# teatimer.net
KiCad netlist of a schematic drawn in EAGLE
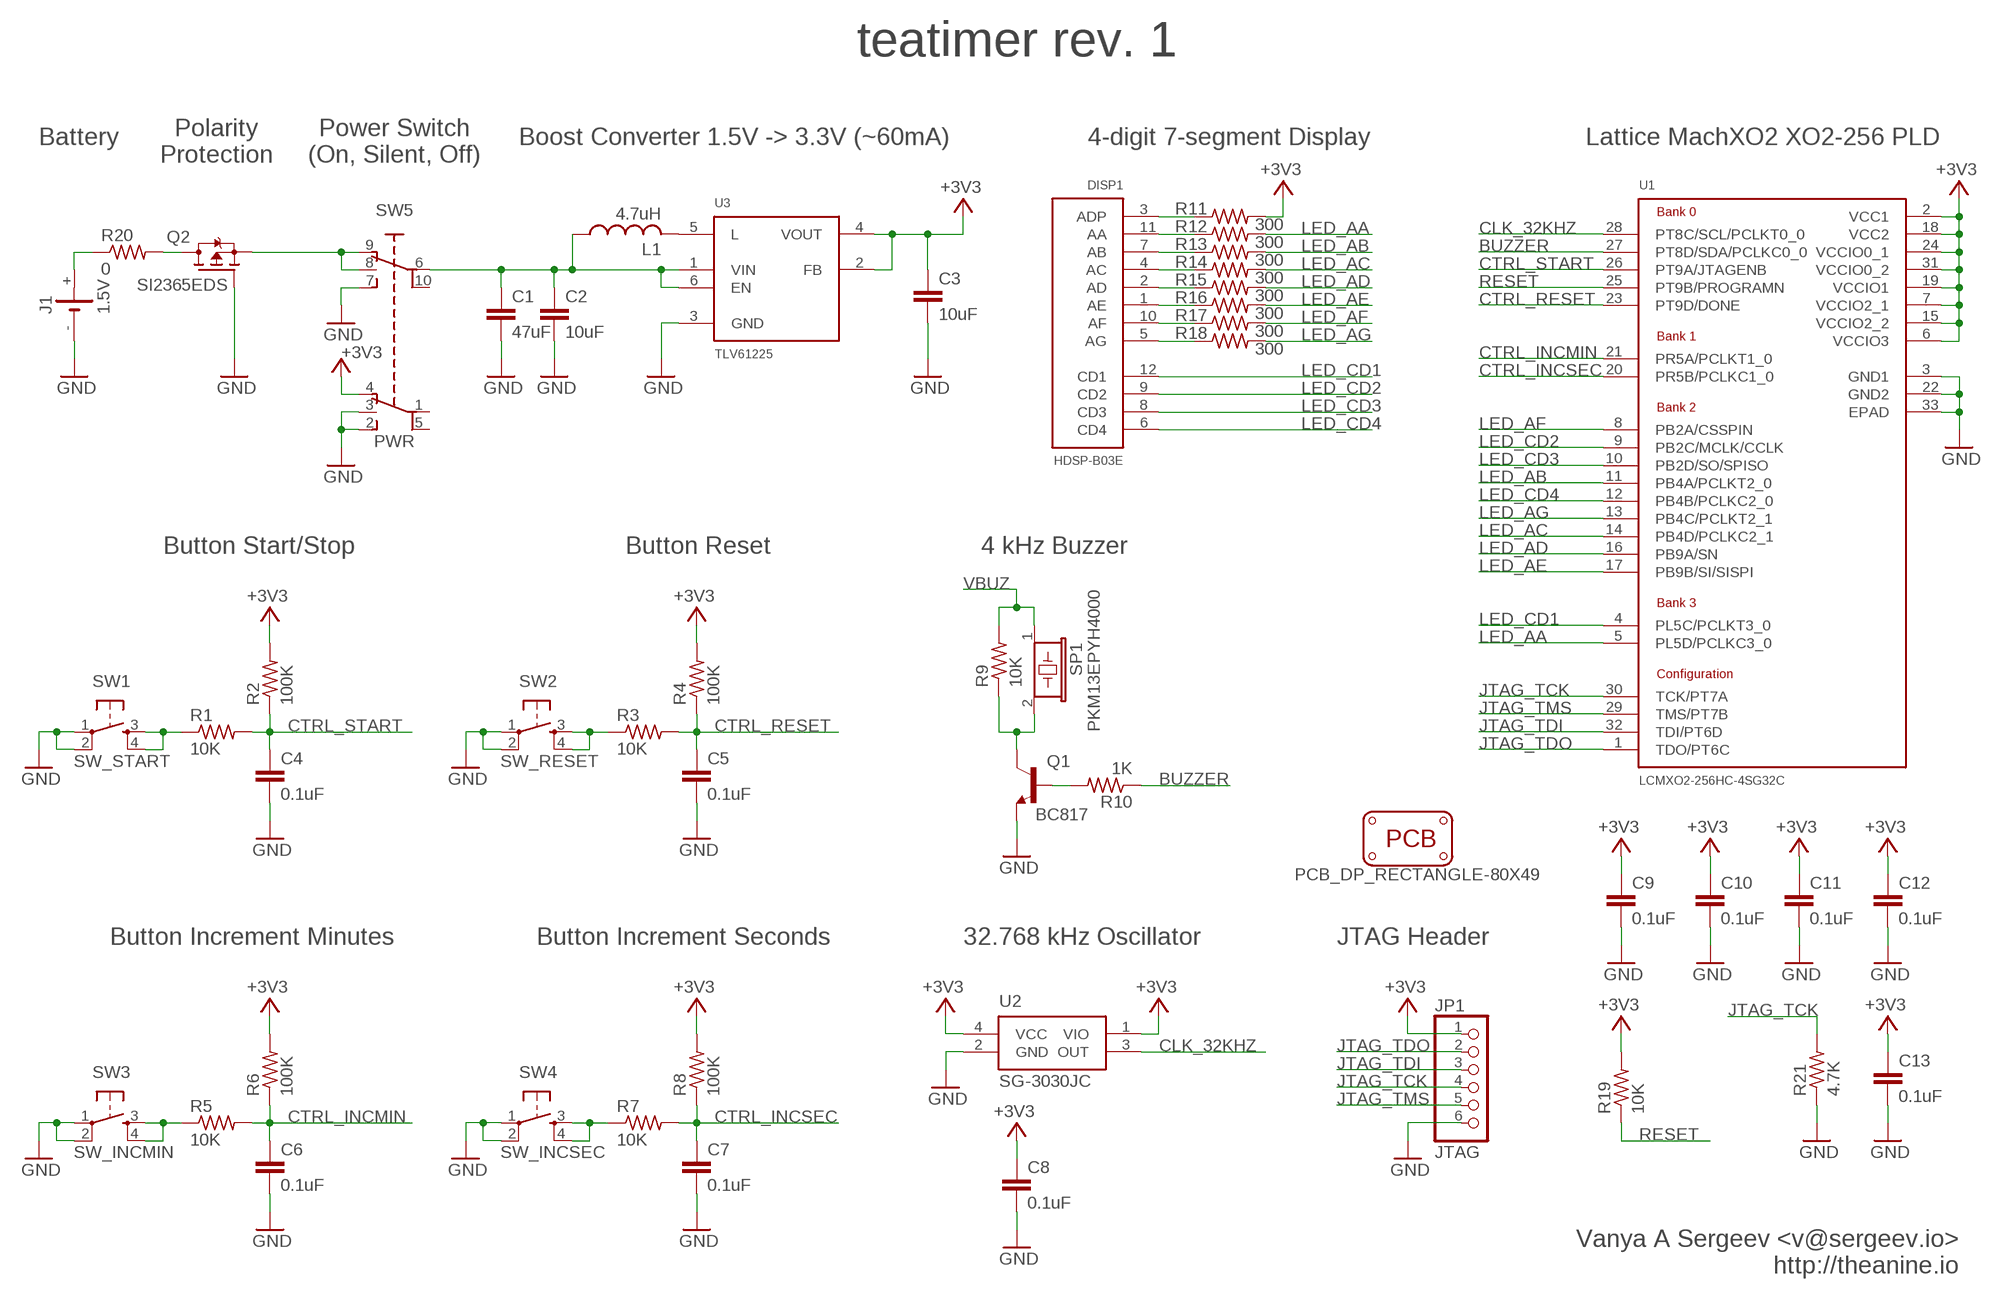
[diagram p0: schematic, sheet 1]

(export (version "E")
  (design (tool "Eeschema 10.0.6"))
  (components
    (comp (ref "C1")
      (value "47uF")
      (footprint "eagle-import:C0805")
      (libsource (lib "eagle-import") (part "C-EUC0805"))
    )
    (comp (ref "C2")
      (value "10uF")
      (footprint "eagle-import:C0603")
      (libsource (lib "eagle-import") (part "C-EUC0603"))
    )
    (comp (ref "C3")
      (value "10uF")
      (footprint "eagle-import:C0603")
      (libsource (lib "eagle-import") (part "C-EUC0603"))
    )
    (comp (ref "C4")
      (value "0.1uF")
      (footprint "eagle-import:C0603")
      (libsource (lib "eagle-import") (part "C-EUC0603"))
    )
    (comp (ref "C5")
      (value "0.1uF")
      (footprint "eagle-import:C0603")
      (libsource (lib "eagle-import") (part "C-EUC0603"))
    )
    (comp (ref "C6")
      (value "0.1uF")
      (footprint "eagle-import:C0603")
      (libsource (lib "eagle-import") (part "C-EUC0603"))
    )
    (comp (ref "C7")
      (value "0.1uF")
      (footprint "eagle-import:C0603")
      (libsource (lib "eagle-import") (part "C-EUC0603"))
    )
    (comp (ref "C8")
      (value "0.1uF")
      (footprint "eagle-import:C0603")
      (libsource (lib "eagle-import") (part "C-EUC0603"))
    )
    (comp (ref "C9")
      (value "0.1uF")
      (footprint "eagle-import:C0603")
      (libsource (lib "eagle-import") (part "C-EUC0603"))
    )
    (comp (ref "C10")
      (value "0.1uF")
      (footprint "eagle-import:C0603")
      (libsource (lib "eagle-import") (part "C-EUC0603"))
    )
    (comp (ref "C11")
      (value "0.1uF")
      (footprint "eagle-import:C0603")
      (libsource (lib "eagle-import") (part "C-EUC0603"))
    )
    (comp (ref "C12")
      (value "0.1uF")
      (footprint "eagle-import:C0603")
      (libsource (lib "eagle-import") (part "C-EUC0603"))
    )
    (comp (ref "C13")
      (value "0.1uF")
      (footprint "eagle-import:C0603")
      (libsource (lib "eagle-import") (part "C-EUC0603"))
    )
    (comp (ref "DISP1")
      (value "HDSP-B03E")
      (footprint "eagle-import:HDSP-B0XE")
      (libsource (lib "eagle-import") (part "HDSP-B03E"))
    )
    (comp (ref "J1")
      (value "1.5V")
      (footprint "eagle-import:AAA-2466")
      (libsource (lib "eagle-import") (part "BAT-HOLDER-AAA"))
    )
    (comp (ref "JP1")
      (value "JTAG")
      (footprint "eagle-import:1X06_90-SMD")
      (libsource (lib "eagle-import") (part "PINHD-1X6"))
    )
    (comp (ref "L1")
      (value "4.7uH")
      (footprint "eagle-import:L2520")
      (libsource (lib "eagle-import") (part "CIG22L"))
    )
    (comp (ref "PCB1")
      (value "PCB_DP_RECTANGLE-80X49")
      (footprint "eagle-import:DP8049_V1")
      (libsource (lib "eagle-import") (part "PCB_DP_RECTANGLE-80X49"))
    )
    (comp (ref "Q1")
      (value "BC817")
      (footprint "eagle-import:SOT23-BEC")
      (libsource (lib "eagle-import") (part "BC817SMD-40"))
    )
    (comp (ref "Q2")
      (value "SI2365EDS")
      (footprint "eagle-import:SOT23")
      (libsource (lib "eagle-import") (part "SI2365EDS"))
    )
    (comp (ref "R1")
      (value "10K")
      (footprint "eagle-import:R0603")
      (libsource (lib "eagle-import") (part "R-US_R0603"))
    )
    (comp (ref "R2")
      (value "100K")
      (footprint "eagle-import:R0603")
      (libsource (lib "eagle-import") (part "R-US_R0603"))
    )
    (comp (ref "R3")
      (value "10K")
      (footprint "eagle-import:R0603")
      (libsource (lib "eagle-import") (part "R-US_R0603"))
    )
    (comp (ref "R4")
      (value "100K")
      (footprint "eagle-import:R0603")
      (libsource (lib "eagle-import") (part "R-US_R0603"))
    )
    (comp (ref "R5")
      (value "10K")
      (footprint "eagle-import:R0603")
      (libsource (lib "eagle-import") (part "R-US_R0603"))
    )
    (comp (ref "R6")
      (value "100K")
      (footprint "eagle-import:R0603")
      (libsource (lib "eagle-import") (part "R-US_R0603"))
    )
    (comp (ref "R7")
      (value "10K")
      (footprint "eagle-import:R0603")
      (libsource (lib "eagle-import") (part "R-US_R0603"))
    )
    (comp (ref "R8")
      (value "100K")
      (footprint "eagle-import:R0603")
      (libsource (lib "eagle-import") (part "R-US_R0603"))
    )
    (comp (ref "R9")
      (value "10K")
      (footprint "eagle-import:R0603")
      (libsource (lib "eagle-import") (part "R-US_R0603"))
    )
    (comp (ref "R10")
      (value "1K")
      (footprint "eagle-import:R0603")
      (libsource (lib "eagle-import") (part "R-US_R0603"))
    )
    (comp (ref "R11")
      (value "300")
      (footprint "eagle-import:R0603")
      (libsource (lib "eagle-import") (part "R-US_R0603"))
    )
    (comp (ref "R12")
      (value "300")
      (footprint "eagle-import:R0603")
      (libsource (lib "eagle-import") (part "R-US_R0603"))
    )
    (comp (ref "R13")
      (value "300")
      (footprint "eagle-import:R0603")
      (libsource (lib "eagle-import") (part "R-US_R0603"))
    )
    (comp (ref "R14")
      (value "300")
      (footprint "eagle-import:R0603")
      (libsource (lib "eagle-import") (part "R-US_R0603"))
    )
    (comp (ref "R15")
      (value "300")
      (footprint "eagle-import:R0603")
      (libsource (lib "eagle-import") (part "R-US_R0603"))
    )
    (comp (ref "R16")
      (value "300")
      (footprint "eagle-import:R0603")
      (libsource (lib "eagle-import") (part "R-US_R0603"))
    )
    (comp (ref "R17")
      (value "300")
      (footprint "eagle-import:R0603")
      (libsource (lib "eagle-import") (part "R-US_R0603"))
    )
    (comp (ref "R18")
      (value "300")
      (footprint "eagle-import:R0603")
      (libsource (lib "eagle-import") (part "R-US_R0603"))
    )
    (comp (ref "R19")
      (value "10K")
      (footprint "eagle-import:R0603")
      (libsource (lib "eagle-import") (part "R-US_R0603"))
    )
    (comp (ref "R20")
      (value "0")
      (footprint "eagle-import:R0603")
      (libsource (lib "eagle-import") (part "R-US_R0603"))
    )
    (comp (ref "R21")
      (value "4.7K")
      (footprint "eagle-import:R0603")
      (libsource (lib "eagle-import") (part "R-US_R0603"))
    )
    (comp (ref "SP1")
      (value "PKM13EPYH4000")
      (footprint "eagle-import:PKM13EPYH4000")
      (libsource (lib "eagle-import") (part "PKM13EPYH4000"))
    )
    (comp (ref "SW1")
      (value "SW_START")
      (footprint "eagle-import:PTS645")
      (libsource (lib "eagle-import") (part "PTS645"))
    )
    (comp (ref "SW2")
      (value "SW_RESET")
      (footprint "eagle-import:PTS645")
      (libsource (lib "eagle-import") (part "PTS645"))
    )
    (comp (ref "SW3")
      (value "SW_INCMIN")
      (footprint "eagle-import:PTS645")
      (libsource (lib "eagle-import") (part "PTS645"))
    )
    (comp (ref "SW4")
      (value "SW_INCSEC")
      (footprint "eagle-import:PTS645")
      (libsource (lib "eagle-import") (part "PTS645"))
    )
    (comp (ref "SW5")
      (value "PWR")
      (footprint "eagle-import:OS203011MV9QN1")
      (libsource (lib "eagle-import") (part "OS203011MV9QN1"))
    )
    (comp (ref "U1")
      (value "LCMXO2-256HC-4SG32C")
      (footprint "eagle-import:QFN32G-0.5-5X5MM")
      (libsource (lib "eagle-import") (part "LCMXO2-256HC-4SG32C"))
    )
    (comp (ref "U2")
      (value "SG-3030JC")
      (footprint "eagle-import:SG-3030JC")
      (libsource (lib "eagle-import") (part "SG-3030JC"))
    )
    (comp (ref "U3")
      (value "TLV61225")
      (footprint "eagle-import:SC70-6L")
      (libsource (lib "eagle-import") (part "TLV61225"))
    )
  )
  (nets
    (net (code "1") (name "+3V3") (class "Default")
      (node (ref "C10") (pin "1") (pinfunction "1_1") (pintype "passive"))
      (node (ref "C11") (pin "1") (pinfunction "1_1") (pintype "passive"))
      (node (ref "C12") (pin "1") (pinfunction "1_1") (pintype "passive"))
      (node (ref "C13") (pin "1") (pinfunction "1_1") (pintype "passive"))
      (node (ref "C3") (pin "1") (pinfunction "1_1") (pintype "passive"))
      (node (ref "C8") (pin "1") (pinfunction "1_1") (pintype "passive"))
      (node (ref "C9") (pin "1") (pinfunction "1_1") (pintype "passive"))
      (node (ref "JP1") (pin "1") (pinfunction "1_1") (pintype "passive"))
      (node (ref "R11") (pin "2") (pinfunction "2_2") (pintype "passive"))
      (node (ref "R19") (pin "2") (pinfunction "2_2") (pintype "passive"))
      (node (ref "R2") (pin "2") (pinfunction "2_2") (pintype "passive"))
      (node (ref "R4") (pin "2") (pinfunction "2_2") (pintype "passive"))
      (node (ref "R6") (pin "2") (pinfunction "2_2") (pintype "passive"))
      (node (ref "R8") (pin "2") (pinfunction "2_2") (pintype "passive"))
      (node (ref "SW5") (pin "4") (pinfunction "B1_4") (pintype "passive"))
      (node (ref "U1") (pin "15") (pinfunction "VCCIO2_2_15") (pintype "bidirectional"))
      (node (ref "U1") (pin "18") (pinfunction "VCC2_18") (pintype "bidirectional"))
      (node (ref "U1") (pin "19") (pinfunction "VCCIO1_19") (pintype "bidirectional"))
      (node (ref "U1") (pin "2") (pinfunction "VCC1_2") (pintype "bidirectional"))
      (node (ref "U1") (pin "24") (pinfunction "VCCIO0_1_24") (pintype "bidirectional"))
      (node (ref "U1") (pin "31") (pinfunction "VCCIO0_2_31") (pintype "bidirectional"))
      (node (ref "U1") (pin "6") (pinfunction "VCCIO3_6") (pintype "bidirectional"))
      (node (ref "U1") (pin "7") (pinfunction "VCCIO2_1_7") (pintype "bidirectional"))
      (node (ref "U2") (pin "1") (pinfunction "VIO_1") (pintype "bidirectional"))
      (node (ref "U2") (pin "4") (pinfunction "VCC_4") (pintype "bidirectional"))
      (node (ref "U3") (pin "2") (pinfunction "FB_2") (pintype "bidirectional"))
      (node (ref "U3") (pin "4") (pinfunction "VOUT_4") (pintype "bidirectional"))
    )
    (net (code "2") (name "/BUZZER") (class "Default")
      (node (ref "R10") (pin "1") (pinfunction "1_1") (pintype "passive"))
      (node (ref "U1") (pin "27") (pinfunction "PT8D/SDA/PCLKC0_0_27") (pintype "bidirectional"))
    )
    (net (code "3") (name "/CLK_32KHZ") (class "Default")
      (node (ref "U1") (pin "28") (pinfunction "PT8C/SCL/PCLKT0_0_28") (pintype "bidirectional"))
      (node (ref "U2") (pin "3") (pinfunction "OUT_3") (pintype "bidirectional"))
    )
    (net (code "4") (name "/CTRL_INCMIN") (class "Default")
      (node (ref "C6") (pin "1") (pinfunction "1_1") (pintype "passive"))
      (node (ref "R5") (pin "2") (pinfunction "2_2") (pintype "passive"))
      (node (ref "R6") (pin "1") (pinfunction "1_1") (pintype "passive"))
      (node (ref "U1") (pin "21") (pinfunction "PR5A/PCLKT1_0_21") (pintype "bidirectional"))
    )
    (net (code "5") (name "/CTRL_INCSEC") (class "Default")
      (node (ref "C7") (pin "1") (pinfunction "1_1") (pintype "passive"))
      (node (ref "R7") (pin "2") (pinfunction "2_2") (pintype "passive"))
      (node (ref "R8") (pin "1") (pinfunction "1_1") (pintype "passive"))
      (node (ref "U1") (pin "20") (pinfunction "PR5B/PCLKC1_0_20") (pintype "bidirectional"))
    )
    (net (code "6") (name "/CTRL_RESET") (class "Default")
      (node (ref "C5") (pin "1") (pinfunction "1_1") (pintype "passive"))
      (node (ref "R3") (pin "2") (pinfunction "2_2") (pintype "passive"))
      (node (ref "R4") (pin "1") (pinfunction "1_1") (pintype "passive"))
      (node (ref "U1") (pin "23") (pinfunction "PT9D/DONE_23") (pintype "bidirectional"))
    )
    (net (code "7") (name "/CTRL_START") (class "Default")
      (node (ref "C4") (pin "1") (pinfunction "1_1") (pintype "passive"))
      (node (ref "R1") (pin "2") (pinfunction "2_2") (pintype "passive"))
      (node (ref "R2") (pin "1") (pinfunction "1_1") (pintype "passive"))
      (node (ref "U1") (pin "26") (pinfunction "PT9A/JTAGENB_26") (pintype "bidirectional"))
    )
    (net (code "8") (name "/JTAG_TCK") (class "Default")
      (node (ref "JP1") (pin "4") (pinfunction "4_4") (pintype "passive"))
      (node (ref "R21") (pin "2") (pinfunction "2_2") (pintype "passive"))
      (node (ref "U1") (pin "30") (pinfunction "TCK/PT7A_30") (pintype "bidirectional"))
    )
    (net (code "9") (name "/JTAG_TDI") (class "Default")
      (node (ref "JP1") (pin "3") (pinfunction "3_3") (pintype "passive"))
      (node (ref "U1") (pin "32") (pinfunction "TDI/PT6D_32") (pintype "bidirectional"))
    )
    (net (code "10") (name "/JTAG_TDO") (class "Default")
      (node (ref "JP1") (pin "2") (pinfunction "2_2") (pintype "passive"))
      (node (ref "U1") (pin "1") (pinfunction "TDO/PT6C_1") (pintype "bidirectional"))
    )
    (net (code "11") (name "/JTAG_TMS") (class "Default")
      (node (ref "JP1") (pin "5") (pinfunction "5_5") (pintype "passive"))
      (node (ref "U1") (pin "29") (pinfunction "TMS/PT7B_29") (pintype "bidirectional"))
    )
    (net (code "12") (name "/LED_AA") (class "Default")
      (node (ref "R12") (pin "2") (pinfunction "2_2") (pintype "passive"))
      (node (ref "U1") (pin "5") (pinfunction "PL5D/PCLKC3_0_5") (pintype "bidirectional"))
    )
    (net (code "13") (name "/LED_AB") (class "Default")
      (node (ref "R13") (pin "2") (pinfunction "2_2") (pintype "passive"))
      (node (ref "U1") (pin "11") (pinfunction "PB4A/PCLKT2_0_11") (pintype "bidirectional"))
    )
    (net (code "14") (name "/LED_AC") (class "Default")
      (node (ref "R14") (pin "2") (pinfunction "2_2") (pintype "passive"))
      (node (ref "U1") (pin "14") (pinfunction "PB4D/PCLKC2_1_14") (pintype "bidirectional"))
    )
    (net (code "15") (name "/LED_AD") (class "Default")
      (node (ref "R15") (pin "2") (pinfunction "2_2") (pintype "passive"))
      (node (ref "U1") (pin "16") (pinfunction "PB9A/SN_16") (pintype "bidirectional"))
    )
    (net (code "16") (name "/LED_AE") (class "Default")
      (node (ref "R16") (pin "2") (pinfunction "2_2") (pintype "passive"))
      (node (ref "U1") (pin "17") (pinfunction "PB9B/SI/SISPI_17") (pintype "bidirectional"))
    )
    (net (code "17") (name "/LED_AF") (class "Default")
      (node (ref "R17") (pin "2") (pinfunction "2_2") (pintype "passive"))
      (node (ref "U1") (pin "8") (pinfunction "PB2A/CSSPIN_8") (pintype "bidirectional"))
    )
    (net (code "18") (name "/LED_AG") (class "Default")
      (node (ref "R18") (pin "2") (pinfunction "2_2") (pintype "passive"))
      (node (ref "U1") (pin "13") (pinfunction "PB4C/PCLKT2_1_13") (pintype "bidirectional"))
    )
    (net (code "19") (name "/LED_CD1") (class "Default")
      (node (ref "DISP1") (pin "12") (pinfunction "CD1_12") (pintype "bidirectional"))
      (node (ref "U1") (pin "4") (pinfunction "PL5C/PCLKT3_0_4") (pintype "bidirectional"))
    )
    (net (code "20") (name "/LED_CD2") (class "Default")
      (node (ref "DISP1") (pin "9") (pinfunction "CD2_9") (pintype "bidirectional"))
      (node (ref "U1") (pin "9") (pinfunction "PB2C/MCLK/CCLK_9") (pintype "bidirectional"))
    )
    (net (code "21") (name "/LED_CD3") (class "Default")
      (node (ref "DISP1") (pin "8") (pinfunction "CD3_8") (pintype "bidirectional"))
      (node (ref "U1") (pin "10") (pinfunction "PB2D/SO/SPISO_10") (pintype "bidirectional"))
    )
    (net (code "22") (name "/LED_CD4") (class "Default")
      (node (ref "DISP1") (pin "6") (pinfunction "CD4_6") (pintype "bidirectional"))
      (node (ref "U1") (pin "12") (pinfunction "PB4B/PCLKC2_0_12") (pintype "bidirectional"))
    )
    (net (code "23") (name "/RESET") (class "Default")
      (node (ref "R19") (pin "1") (pinfunction "1_1") (pintype "passive"))
      (node (ref "U1") (pin "25") (pinfunction "PT9B/PROGRAMN_25") (pintype "bidirectional"))
    )
    (net (code "24") (name "/VBUZ") (class "Default")
      (node (ref "R9") (pin "2") (pinfunction "2_2") (pintype "passive"))
      (node (ref "SP1") (pin "1") (pinfunction "1_1") (pintype "passive"))
    )
    (net (code "25") (name "GND") (class "Default")
      (node (ref "C1") (pin "2") (pinfunction "2_2") (pintype "passive"))
      (node (ref "C10") (pin "2") (pinfunction "2_2") (pintype "passive"))
      (node (ref "C11") (pin "2") (pinfunction "2_2") (pintype "passive"))
      (node (ref "C12") (pin "2") (pinfunction "2_2") (pintype "passive"))
      (node (ref "C13") (pin "2") (pinfunction "2_2") (pintype "passive"))
      (node (ref "C2") (pin "2") (pinfunction "2_2") (pintype "passive"))
      (node (ref "C3") (pin "2") (pinfunction "2_2") (pintype "passive"))
      (node (ref "C4") (pin "2") (pinfunction "2_2") (pintype "passive"))
      (node (ref "C5") (pin "2") (pinfunction "2_2") (pintype "passive"))
      (node (ref "C6") (pin "2") (pinfunction "2_2") (pintype "passive"))
      (node (ref "C7") (pin "2") (pinfunction "2_2") (pintype "passive"))
      (node (ref "C8") (pin "2") (pinfunction "2_2") (pintype "passive"))
      (node (ref "C9") (pin "2") (pinfunction "2_2") (pintype "passive"))
      (node (ref "J1") (pin "-") (pinfunction "-_-") (pintype "passive"))
      (node (ref "JP1") (pin "6") (pinfunction "6_6") (pintype "passive"))
      (node (ref "Q1") (pin "E") (pinfunction "E_E") (pintype "passive"))
      (node (ref "Q2") (pin "1") (pinfunction "G_1") (pintype "passive"))
      (node (ref "R21") (pin "1") (pinfunction "1_1") (pintype "passive"))
      (node (ref "SW1") (pin "1") (pinfunction "P_1") (pintype "passive"))
      (node (ref "SW1") (pin "2") (pinfunction "P1_2") (pintype "passive"))
      (node (ref "SW2") (pin "1") (pinfunction "P_1") (pintype "passive"))
      (node (ref "SW2") (pin "2") (pinfunction "P1_2") (pintype "passive"))
      (node (ref "SW3") (pin "1") (pinfunction "P_1") (pintype "passive"))
      (node (ref "SW3") (pin "2") (pinfunction "P1_2") (pintype "passive"))
      (node (ref "SW4") (pin "1") (pinfunction "P_1") (pintype "passive"))
      (node (ref "SW4") (pin "2") (pinfunction "P1_2") (pintype "passive"))
      (node (ref "SW5") (pin "2") (pinfunction "B3_2") (pintype "passive"))
      (node (ref "SW5") (pin "3") (pinfunction "B2_3") (pintype "passive"))
      (node (ref "SW5") (pin "7") (pinfunction "A3_7") (pintype "passive"))
      (node (ref "U1") (pin "22") (pinfunction "GND2_22") (pintype "bidirectional"))
      (node (ref "U1") (pin "3") (pinfunction "GND1_3") (pintype "bidirectional"))
      (node (ref "U1") (pin "33") (pinfunction "EPAD_33") (pintype "bidirectional"))
      (node (ref "U2") (pin "2") (pinfunction "GND_2") (pintype "bidirectional"))
      (node (ref "U3") (pin "3") (pinfunction "GND_3") (pintype "bidirectional"))
    )
    (net (code "26") (name "Net-(DISP1-AA)") (class "Default")
      (node (ref "DISP1") (pin "11") (pinfunction "AA_11") (pintype "bidirectional"))
      (node (ref "R12") (pin "1") (pinfunction "1_1") (pintype "passive"))
    )
    (net (code "27") (name "Net-(DISP1-AB)") (class "Default")
      (node (ref "DISP1") (pin "7") (pinfunction "AB_7") (pintype "bidirectional"))
      (node (ref "R13") (pin "1") (pinfunction "1_1") (pintype "passive"))
    )
    (net (code "28") (name "Net-(DISP1-AC)") (class "Default")
      (node (ref "DISP1") (pin "4") (pinfunction "AC_4") (pintype "bidirectional"))
      (node (ref "R14") (pin "1") (pinfunction "1_1") (pintype "passive"))
    )
    (net (code "29") (name "Net-(DISP1-AD)") (class "Default")
      (node (ref "DISP1") (pin "2") (pinfunction "AD_2") (pintype "bidirectional"))
      (node (ref "R15") (pin "1") (pinfunction "1_1") (pintype "passive"))
    )
    (net (code "30") (name "Net-(DISP1-ADP)") (class "Default")
      (node (ref "DISP1") (pin "3") (pinfunction "ADP_3") (pintype "bidirectional"))
      (node (ref "R11") (pin "1") (pinfunction "1_1") (pintype "passive"))
    )
    (net (code "31") (name "Net-(DISP1-AE)") (class "Default")
      (node (ref "DISP1") (pin "1") (pinfunction "AE_1") (pintype "bidirectional"))
      (node (ref "R16") (pin "1") (pinfunction "1_1") (pintype "passive"))
    )
    (net (code "32") (name "Net-(DISP1-AF)") (class "Default")
      (node (ref "DISP1") (pin "10") (pinfunction "AF_10") (pintype "bidirectional"))
      (node (ref "R17") (pin "1") (pinfunction "1_1") (pintype "passive"))
    )
    (net (code "33") (name "Net-(DISP1-AG)") (class "Default")
      (node (ref "DISP1") (pin "5") (pinfunction "AG_5") (pintype "bidirectional"))
      (node (ref "R18") (pin "1") (pinfunction "1_1") (pintype "passive"))
    )
    (net (code "34") (name "Net-(J1-Pad+)") (class "Default")
      (node (ref "J1") (pin "+") (pinfunction "+_+") (pintype "passive"))
      (node (ref "R20") (pin "1") (pinfunction "1_1") (pintype "passive"))
    )
    (net (code "35") (name "Net-(Q1-PadB)") (class "Default")
      (node (ref "Q1") (pin "B") (pinfunction "B_B") (pintype "passive"))
      (node (ref "R10") (pin "2") (pinfunction "2_2") (pintype "passive"))
    )
    (net (code "36") (name "Net-(Q1-PadC)") (class "Default")
      (node (ref "Q1") (pin "C") (pinfunction "C_C") (pintype "passive"))
      (node (ref "R9") (pin "1") (pinfunction "1_1") (pintype "passive"))
      (node (ref "SP1") (pin "2") (pinfunction "2_2") (pintype "passive"))
    )
    (net (code "37") (name "Net-(Q2-D)") (class "Default")
      (node (ref "Q2") (pin "3") (pinfunction "D_3") (pintype "passive"))
      (node (ref "R20") (pin "2") (pinfunction "2_2") (pintype "passive"))
    )
    (net (code "38") (name "Net-(Q2-S)") (class "Default")
      (node (ref "Q2") (pin "2") (pinfunction "S_2") (pintype "passive"))
      (node (ref "SW5") (pin "8") (pinfunction "A2_8") (pintype "passive"))
      (node (ref "SW5") (pin "9") (pinfunction "A1_9") (pintype "passive"))
    )
    (net (code "39") (name "Net-(SW1-S)") (class "Default")
      (node (ref "R1") (pin "1") (pinfunction "1_1") (pintype "passive"))
      (node (ref "SW1") (pin "3") (pinfunction "S_3") (pintype "passive"))
      (node (ref "SW1") (pin "4") (pinfunction "S1_4") (pintype "passive"))
    )
    (net (code "40") (name "Net-(SW2-S)") (class "Default")
      (node (ref "R3") (pin "1") (pinfunction "1_1") (pintype "passive"))
      (node (ref "SW2") (pin "3") (pinfunction "S_3") (pintype "passive"))
      (node (ref "SW2") (pin "4") (pinfunction "S1_4") (pintype "passive"))
    )
    (net (code "41") (name "Net-(SW3-S)") (class "Default")
      (node (ref "R5") (pin "1") (pinfunction "1_1") (pintype "passive"))
      (node (ref "SW3") (pin "3") (pinfunction "S_3") (pintype "passive"))
      (node (ref "SW3") (pin "4") (pinfunction "S1_4") (pintype "passive"))
    )
    (net (code "42") (name "Net-(SW4-S)") (class "Default")
      (node (ref "R7") (pin "1") (pinfunction "1_1") (pintype "passive"))
      (node (ref "SW4") (pin "3") (pinfunction "S_3") (pintype "passive"))
      (node (ref "SW4") (pin "4") (pinfunction "S1_4") (pintype "passive"))
    )
    (net (code "43") (name "Net-(SW5-P1)") (class "Default")
      (node (ref "C1") (pin "1") (pinfunction "1_1") (pintype "passive"))
      (node (ref "C2") (pin "1") (pinfunction "1_1") (pintype "passive"))
      (node (ref "L1") (pin "1") (pinfunction "1_1") (pintype "passive"))
      (node (ref "SW5") (pin "6") (pinfunction "P1_6") (pintype "passive"))
      (node (ref "U3") (pin "1") (pinfunction "VIN_1") (pintype "bidirectional"))
      (node (ref "U3") (pin "6") (pinfunction "EN_6") (pintype "bidirectional"))
    )
    (net (code "44") (name "Net-(U3-L)") (class "Default")
      (node (ref "L1") (pin "2") (pinfunction "2_2") (pintype "passive"))
      (node (ref "U3") (pin "5") (pinfunction "L_5") (pintype "bidirectional"))
    )
    (net (code "45") (name "unconnected-(SW5-P2-Pad10)") (class "Default")
      (node (ref "SW5") (pin "10") (pinfunction "P2_10") (pintype "passive"))
    )
    (net (code "46") (name "unconnected-(SW5-Q1-Pad1)") (class "Default")
      (node (ref "SW5") (pin "1") (pinfunction "Q1_1") (pintype "passive"))
    )
    (net (code "47") (name "unconnected-(SW5-Q2-Pad5)") (class "Default")
      (node (ref "SW5") (pin "5") (pinfunction "Q2_5") (pintype "passive"))
    )
  )
)
